# Split12VoltForTesting.net
KiCad netlist of a schematic drawn in EAGLE
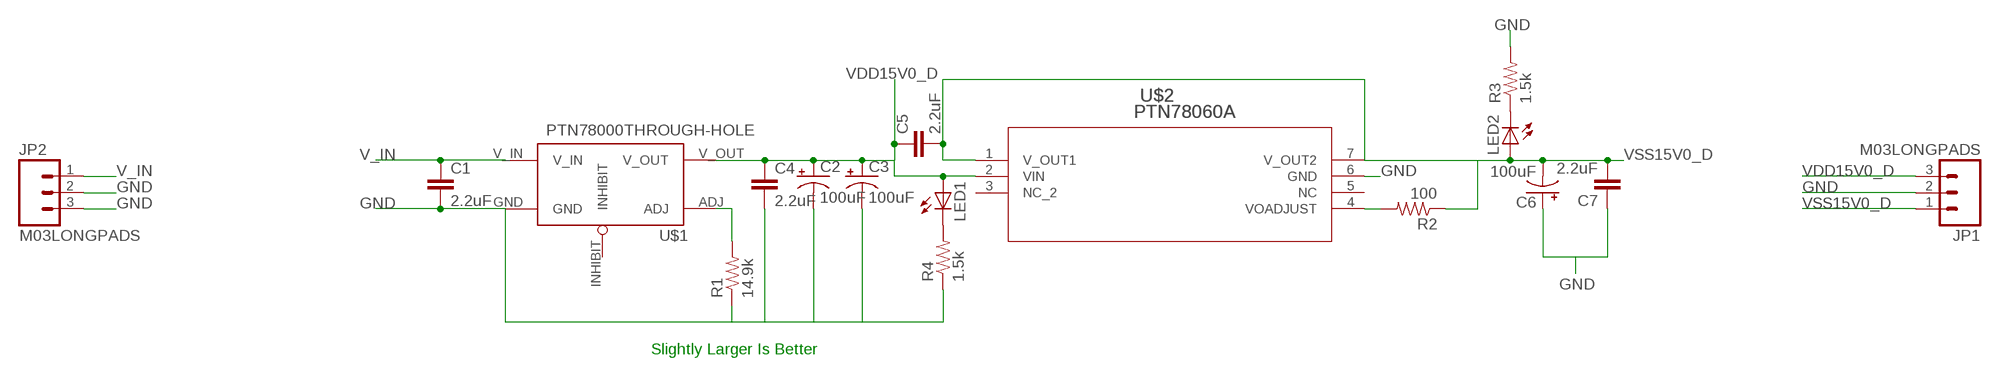
[diagram p0: schematic, sheet 1]

(export (version "E")
  (design (tool "Eeschema 10.0.6"))
  (components
    (comp (ref "C1")
      (value "2.2uF")
      (footprint "eagle-import:1210")
      (libsource (lib "eagle-import") (part "CAP1210"))
    )
    (comp (ref "C2")
      (value "100uF")
      (footprint "eagle-import:CPOL-RADIAL-100UF-25V")
      (libsource (lib "eagle-import") (part "CAP_POLPTH1"))
    )
    (comp (ref "C3")
      (value "100uF")
      (footprint "eagle-import:CPOL-RADIAL-100UF-25V")
      (libsource (lib "eagle-import") (part "CAP_POLPTH1"))
    )
    (comp (ref "C4")
      (value "2.2uF")
      (footprint "eagle-import:1210")
      (libsource (lib "eagle-import") (part "CAP1210"))
    )
    (comp (ref "C5")
      (value "2.2uF")
      (footprint "eagle-import:1210")
      (libsource (lib "eagle-import") (part "CAP1210"))
    )
    (comp (ref "C6")
      (value "100uF")
      (footprint "eagle-import:CPOL-RADIAL-100UF-25V")
      (libsource (lib "eagle-import") (part "CAP_POLPTH1"))
    )
    (comp (ref "C7")
      (value "2.2uF")
      (footprint "eagle-import:1210")
      (libsource (lib "eagle-import") (part "CAP1210"))
    )
    (comp (ref "JP1")
      (value "M03LONGPADS")
      (footprint "eagle-import:1X03_LONGPADS")
      (libsource (lib "eagle-import") (part "M03LONGPADS"))
    )
    (comp (ref "JP2")
      (value "M03LONGPADS")
      (footprint "eagle-import:1X03_LONGPADS")
      (libsource (lib "eagle-import") (part "M03LONGPADS"))
    )
    (comp (ref "LED1")
      (value "LED0805")
      (footprint "eagle-import:LED-0805")
      (libsource (lib "eagle-import") (part "LED0805"))
    )
    (comp (ref "LED2")
      (value "LED0805")
      (footprint "eagle-import:LED-0805")
      (libsource (lib "eagle-import") (part "LED0805"))
    )
    (comp (ref "R1")
      (value "14.9k")
      (footprint "eagle-import:0805")
      (libsource (lib "eagle-import") (part "RESISTOR0805-RES"))
    )
    (comp (ref "R2")
      (value "100")
      (footprint "eagle-import:0805")
      (libsource (lib "eagle-import") (part "RESISTOR0805-RES"))
    )
    (comp (ref "R3")
      (value "1.5k")
      (footprint "eagle-import:0805")
      (libsource (lib "eagle-import") (part "RESISTOR0805-RES"))
    )
    (comp (ref "R4")
      (value "1.5k")
      (footprint "eagle-import:0805")
      (libsource (lib "eagle-import") (part "RESISTOR0805-RES"))
    )
    (comp (ref "U$1")
      (value "PTN78000THROUGH-HOLE")
      (footprint "eagle-import:PTN78000")
      (libsource (lib "eagle-import") (part "PTN78000THROUGH-HOLE"))
    )
    (comp (ref "U$2")
      (value "PTN78060A")
      (footprint "eagle-import:PTN_EUW")
      (libsource (lib "eagle-import") (part "PTN78060A"))
    )
  )
  (nets
    (net (code "1") (name "/GND") (class "Default")
      (node (ref "C1") (pin "2") (pinfunction "2_2") (pintype "passive"))
      (node (ref "C2") (pin "2") (pinfunction "-_2") (pintype "passive"))
      (node (ref "C3") (pin "2") (pinfunction "-_2") (pintype "passive"))
      (node (ref "C4") (pin "2") (pinfunction "2_2") (pintype "passive"))
      (node (ref "C6") (pin "1") (pinfunction "+_1") (pintype "passive"))
      (node (ref "C7") (pin "1") (pinfunction "1_1") (pintype "passive"))
      (node (ref "JP1") (pin "2") (pinfunction "2_2") (pintype "passive"))
      (node (ref "JP2") (pin "2") (pinfunction "2_2") (pintype "passive"))
      (node (ref "JP2") (pin "3") (pinfunction "3_3") (pintype "passive"))
      (node (ref "R1") (pin "1") (pinfunction "1_1") (pintype "passive"))
      (node (ref "R3") (pin "2") (pinfunction "2_2") (pintype "passive"))
      (node (ref "R4") (pin "1") (pinfunction "1_1") (pintype "passive"))
      (node (ref "U$1") (pin "GND") (pinfunction "GND_GND") (pintype "power_in"))
      (node (ref "U$2") (pin "6") (pinfunction "GND_6") (pintype "passive"))
    )
    (net (code "2") (name "/VDD15V0_D") (class "Default")
      (node (ref "C2") (pin "1") (pinfunction "+_1") (pintype "passive"))
      (node (ref "C3") (pin "1") (pinfunction "+_1") (pintype "passive"))
      (node (ref "C4") (pin "1") (pinfunction "1_1") (pintype "passive"))
      (node (ref "C5") (pin "1") (pinfunction "1_1") (pintype "passive"))
      (node (ref "JP1") (pin "3") (pinfunction "3_3") (pintype "passive"))
      (node (ref "LED1") (pin "1") (pinfunction "A_1") (pintype "passive"))
      (node (ref "U$1") (pin "V_OUT") (pinfunction "V_OUT_V_OUT") (pintype "output"))
      (node (ref "U$2") (pin "2") (pinfunction "VIN_2") (pintype "passive"))
    )
    (net (code "3") (name "/VSS15V0_D") (class "Default")
      (node (ref "C5") (pin "2") (pinfunction "2_2") (pintype "passive"))
      (node (ref "C6") (pin "2") (pinfunction "-_2") (pintype "passive"))
      (node (ref "C7") (pin "2") (pinfunction "2_2") (pintype "passive"))
      (node (ref "JP1") (pin "1") (pinfunction "1_1") (pintype "passive"))
      (node (ref "LED2") (pin "1") (pinfunction "A_1") (pintype "passive"))
      (node (ref "R2") (pin "1") (pinfunction "1_1") (pintype "passive"))
      (node (ref "U$2") (pin "1") (pinfunction "V_OUT1_1") (pintype "passive"))
      (node (ref "U$2") (pin "7") (pinfunction "V_OUT2_7") (pintype "passive"))
    )
    (net (code "4") (name "/V_IN") (class "Default")
      (node (ref "C1") (pin "1") (pinfunction "1_1") (pintype "passive"))
      (node (ref "JP2") (pin "1") (pinfunction "1_1") (pintype "passive"))
      (node (ref "U$1") (pin "V_IN") (pinfunction "V_IN_V_IN") (pintype "power_in"))
    )
    (net (code "5") (name "Net-(LED1-C)") (class "Default")
      (node (ref "LED1") (pin "2") (pinfunction "C_2") (pintype "passive"))
      (node (ref "R4") (pin "2") (pinfunction "2_2") (pintype "passive"))
    )
    (net (code "6") (name "Net-(LED2-C)") (class "Default")
      (node (ref "LED2") (pin "2") (pinfunction "C_2") (pintype "passive"))
      (node (ref "R3") (pin "1") (pinfunction "1_1") (pintype "passive"))
    )
    (net (code "7") (name "Net-(R1-Pad2)") (class "Default")
      (node (ref "R1") (pin "2") (pinfunction "2_2") (pintype "passive"))
      (node (ref "U$1") (pin "ADJ") (pinfunction "ADJ_ADJ") (pintype "input"))
    )
    (net (code "8") (name "Net-(U$2-VOADJUST)") (class "Default")
      (node (ref "R2") (pin "2") (pinfunction "2_2") (pintype "passive"))
      (node (ref "U$2") (pin "4") (pinfunction "VOADJUST_4") (pintype "passive"))
    )
    (net (code "9") (name "unconnected-(U$1-PadINHIBIT)") (class "Default")
      (node (ref "U$1") (pin "INHIBIT") (pinfunction "INHIBIT_INHIBIT") (pintype "input"))
    )
    (net (code "10") (name "unconnected-(U$2-NC-Pad5)") (class "Default")
      (node (ref "U$2") (pin "5") (pinfunction "NC_5") (pintype "passive"))
    )
    (net (code "11") (name "unconnected-(U$2-NC_2-Pad3)") (class "Default")
      (node (ref "U$2") (pin "3") (pinfunction "NC_2_3") (pintype "passive"))
    )
  )
)
